# MCU.net
KiCad netlist of a schematic drawn in Altium Designer
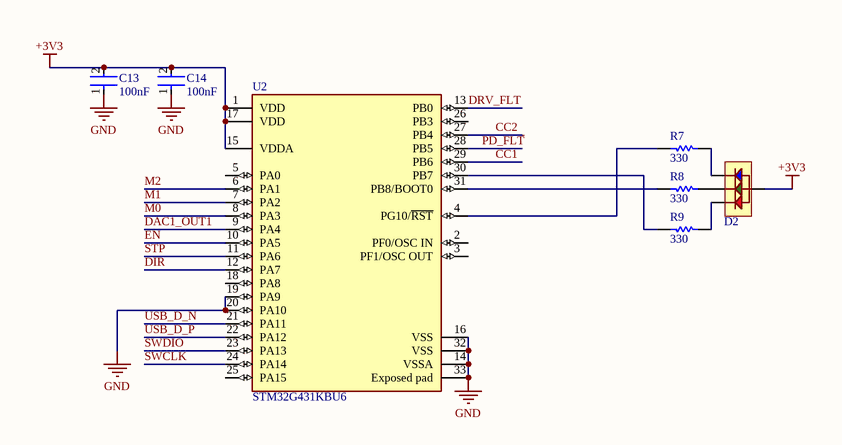
[diagram p0: MCU.SchDoc]

(export (version "E")
  (design (tool "Eeschema 10.0.6"))
  (components
    (comp (ref "C13")
      (value "C1005X7R1H104K050BB")
      (footprint "FP-C1005-050-0_05-IPC_C")
      (description "Multilayer Ceramic Capacitors 100nF ±10% 50V X7R SMD 0402")
      (fields
        (field (name "VOLTAGE") "50V")
        (field (name "CAPACITANCE") "100nF")
        (field (name "TOLERANCE") "10%")
      )
      (libsource (lib "Altium Content Vault") (part "b4654b650e69147ec39a6b967a45e02"))
    )
    (comp (ref "C14")
      (value "C1005X7R1H104K050BB")
      (footprint "FP-C1005-050-0_05-IPC_C")
      (description "Multilayer Ceramic Capacitors 100nF ±10% 50V X7R SMD 0402")
      (fields
        (field (name "VOLTAGE") "50V")
        (field (name "CAPACITANCE") "100nF")
        (field (name "TOLERANCE") "10%")
      )
      (libsource (lib "Altium Content Vault") (part "b4654b650e69147ec39a6b967a45e02"))
    )
    (comp (ref "D2")
      (value "LED-RGB")
      (footprint "XL-2012RGBC")
      (libsource (lib "ParsaLibrary") (part "XL-2012RGBC"))
    )
    (comp (ref "R7")
      (value "ERJ-2GEJ331X")
      (footprint "RESC1005X40X25NL05T05")
      (fields (field (name "MANUFACTURER") "Panasonic") (field (name "RESISTANCE") "330"))
      (libsource (lib "Altium Content Vault") (part "RES"))
    )
    (comp (ref "R8")
      (value "ERJ-2GEJ331X")
      (footprint "RESC1005X40X25NL05T05")
      (fields (field (name "MANUFACTURER") "Panasonic") (field (name "RESISTANCE") "330"))
      (libsource (lib "Altium Content Vault") (part "RES"))
    )
    (comp (ref "R9")
      (value "ERJ-2GEJ331X")
      (footprint "RESC1005X40X25NL05T05")
      (fields (field (name "MANUFACTURER") "Panasonic") (field (name "RESISTANCE") "330"))
      (libsource (lib "Altium Content Vault") (part "RES"))
    )
    (comp (ref "U2")
      (value "STM32G431KBU6")
      (footprint "FP-UFQFPN32-A0B8-IPC_A")
      (description "IC MCU 32BIT 128KB FLSH 32UFQFPN")
      (libsource (lib "Altium Content Vault") (part "b0f9ef315fadbc83d4ed39e8b05710e"))
    )
  )
  (nets
    (net (code "1") (name "+3V3") (class "Default")
      (node (ref "C13") (pin "2") (pinfunction "2_2") (pintype "passive"))
      (node (ref "C14") (pin "2") (pinfunction "2_2") (pintype "passive"))
      (node (ref "D2") (pin "3") (pinfunction "COM_3") (pintype "passive"))
      (node (ref "U2") (pin "1") (pinfunction "VDD_1") (pintype "power_in"))
      (node (ref "U2") (pin "15") (pinfunction "VDDA_15") (pintype "power_in"))
      (node (ref "U2") (pin "17") (pinfunction "VDD_17") (pintype "power_in"))
    )
    (net (code "2") (name "/CC1") (class "Default")
      (node (ref "U2") (pin "29") (pinfunction "PB6_29") (pintype "bidirectional"))
    )
    (net (code "3") (name "/CC2") (class "Default")
      (node (ref "U2") (pin "27") (pinfunction "PB4_27") (pintype "bidirectional"))
    )
    (net (code "4") (name "/DAC1_OUT1") (class "Default")
      (node (ref "U2") (pin "9") (pinfunction "PA4_9") (pintype "bidirectional"))
    )
    (net (code "5") (name "/DIR") (class "Default")
      (node (ref "U2") (pin "12") (pinfunction "PA7_12") (pintype "bidirectional"))
    )
    (net (code "6") (name "/DRV_FLT") (class "Default")
      (node (ref "U2") (pin "13") (pinfunction "PB0_13") (pintype "bidirectional"))
    )
    (net (code "7") (name "/EN") (class "Default")
      (node (ref "U2") (pin "10") (pinfunction "PA5_10") (pintype "bidirectional"))
    )
    (net (code "8") (name "/M0") (class "Default")
      (node (ref "U2") (pin "8") (pinfunction "PA3_8") (pintype "bidirectional"))
    )
    (net (code "9") (name "/M1") (class "Default")
      (node (ref "U2") (pin "7") (pinfunction "PA2_7") (pintype "bidirectional"))
    )
    (net (code "10") (name "/M2") (class "Default")
      (node (ref "U2") (pin "6") (pinfunction "PA1_6") (pintype "bidirectional"))
    )
    (net (code "11") (name "/PD_~{FLT}") (class "Default")
      (node (ref "U2") (pin "28") (pinfunction "PB5_28") (pintype "bidirectional"))
    )
    (net (code "12") (name "/STP") (class "Default")
      (node (ref "U2") (pin "11") (pinfunction "PA6_11") (pintype "bidirectional"))
    )
    (net (code "13") (name "/SWCLK") (class "Default")
      (node (ref "U2") (pin "24") (pinfunction "PA14_24") (pintype "bidirectional"))
    )
    (net (code "14") (name "/SWDIO") (class "Default")
      (node (ref "U2") (pin "23") (pinfunction "PA13_23") (pintype "bidirectional"))
    )
    (net (code "15") (name "/USB_D_N") (class "Default")
      (node (ref "U2") (pin "21") (pinfunction "PA11_21") (pintype "bidirectional"))
    )
    (net (code "16") (name "/USB_D_P") (class "Default")
      (node (ref "U2") (pin "22") (pinfunction "PA12_22") (pintype "bidirectional"))
    )
    (net (code "17") (name "GND") (class "Default")
      (node (ref "C13") (pin "1") (pinfunction "1_1") (pintype "passive"))
      (node (ref "C14") (pin "1") (pinfunction "1_1") (pintype "passive"))
      (node (ref "U2") (pin "14") (pinfunction "VSSA_14") (pintype "power_in"))
      (node (ref "U2") (pin "16") (pinfunction "VSS_16") (pintype "power_in"))
      (node (ref "U2") (pin "19") (pinfunction "PA9_19") (pintype "bidirectional"))
      (node (ref "U2") (pin "20") (pinfunction "PA10_20") (pintype "bidirectional"))
      (node (ref "U2") (pin "32") (pinfunction "VSS_32") (pintype "power_in"))
      (node (ref "U2") (pin "33") (pinfunction "Exposed_pad_33") (pintype "power_in"))
    )
    (net (code "18") (name "Net-(D2-B)") (class "Default")
      (node (ref "D2") (pin "4") (pinfunction "B_4") (pintype "passive"))
      (node (ref "R7") (pin "2") (pinfunction "2_2") (pintype "passive"))
    )
    (net (code "19") (name "Net-(D2-G)") (class "Default")
      (node (ref "D2") (pin "2") (pinfunction "G_2") (pintype "passive"))
      (node (ref "R8") (pin "2") (pinfunction "2_2") (pintype "passive"))
    )
    (net (code "20") (name "Net-(D2-R)") (class "Default")
      (node (ref "D2") (pin "1") (pinfunction "R_1") (pintype "passive"))
      (node (ref "R9") (pin "2") (pinfunction "2_2") (pintype "passive"))
    )
    (net (code "21") (name "Net-(U2-PB7)") (class "Default")
      (node (ref "R9") (pin "1") (pinfunction "1_1") (pintype "passive"))
      (node (ref "U2") (pin "30") (pinfunction "PB7_30") (pintype "bidirectional"))
    )
    (net (code "22") (name "Net-(U2-PB8{slash}BOOT0)") (class "Default")
      (node (ref "R8") (pin "1") (pinfunction "1_1") (pintype "passive"))
      (node (ref "U2") (pin "31") (pinfunction "PB8/BOOT0_31") (pintype "bidirectional"))
    )
    (net (code "23") (name "Net-(U2-PG10{slash}~{RST})") (class "Default")
      (node (ref "R7") (pin "1") (pinfunction "1_1") (pintype "passive"))
      (node (ref "U2") (pin "4") (pinfunction "PG10/~{RST}_4") (pintype "bidirectional"))
    )
    (net (code "24") (name "unconnected-(U2-PA0-Pad5)") (class "Default")
      (node (ref "U2") (pin "5") (pinfunction "PA0_5") (pintype "bidirectional"))
    )
    (net (code "25") (name "unconnected-(U2-PA8-Pad18)") (class "Default")
      (node (ref "U2") (pin "18") (pinfunction "PA8_18") (pintype "bidirectional"))
    )
    (net (code "26") (name "unconnected-(U2-PA15-Pad25)") (class "Default")
      (node (ref "U2") (pin "25") (pinfunction "PA15_25") (pintype "bidirectional"))
    )
    (net (code "27") (name "unconnected-(U2-PB3-Pad26)") (class "Default")
      (node (ref "U2") (pin "26") (pinfunction "PB3_26") (pintype "bidirectional"))
    )
    (net (code "28") (name "unconnected-(U2-PF0{slash}OSC_IN-Pad2)") (class "Default")
      (node (ref "U2") (pin "2") (pinfunction "PF0/OSC_IN_2") (pintype "bidirectional"))
    )
    (net (code "29") (name "unconnected-(U2-PF1{slash}OSC_OUT-Pad3)") (class "Default")
      (node (ref "U2") (pin "3") (pinfunction "PF1/OSC_OUT_3") (pintype "bidirectional"))
    )
  )
)
